# power.net
KiCad netlist of a schematic drawn in Altium Designer
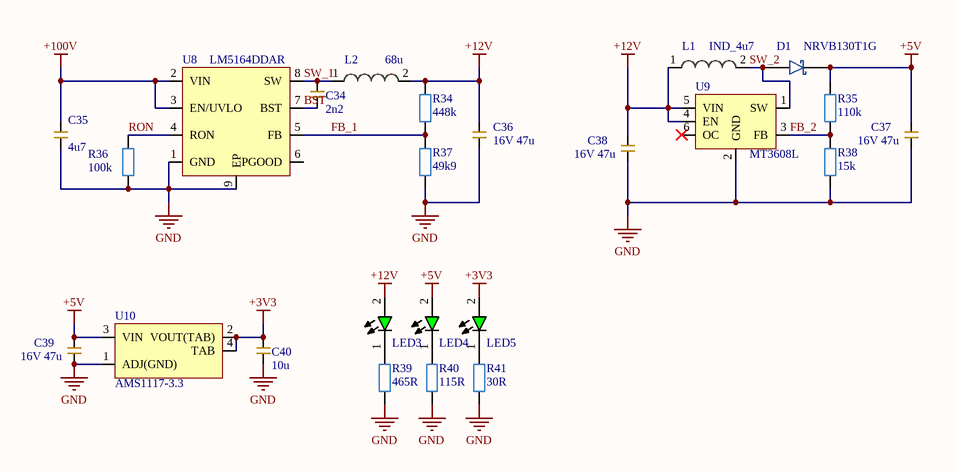
[diagram p0: power.SchDoc]

(export (version "E")
  (design (tool "Eeschema 10.0.6"))
  (components
    (comp (ref "C34")
      (value "2n2")
      (footprint "CAP_0603")
      (description "Multilayer Ceramic Capacitors MLCC - SMD/SMT ROHS")
      (libsource (lib "Passive") (part "CAP_0603"))
    )
    (comp (ref "C35")
      (value "4u7")
      (footprint "FS32X475K101EGG")
      (description "100V 4.7uF X7R ±10% 1210 Multilayer Ceramic Capacitors MLCC - SMD/SMT ROHS")
      (fields
        (field (name "MFR.") "PSA(Prosperity Dielectrics)")
        (field (name "MFR. PART") "FS32X475K101EGG")
      )
      (libsource (lib "Passive") (part "4u7"))
    )
    (comp (ref "C36")
      (value "16V 47u")
      (footprint "CAP_1210")
      (description "16V 47uF X5R ±10% 1210 Multilayer Ceramic Capacitors MLCC - SMD/SMT ROHS")
      (fields (field (name "MFR.") "Murata Electronics") (field (name "MFR. PART") "GRM32ER61C476KE15L"))
      (libsource (lib "Passive") (part "CAP_1210"))
    )
    (comp (ref "C37")
      (value "16V 47u")
      (footprint "CAP_1210")
      (description "16V 47uF X5R ±10% 1210 Multilayer Ceramic Capacitors MLCC - SMD/SMT ROHS")
      (fields (field (name "MFR.") "Murata Electronics") (field (name "MFR. PART") "GRM32ER61C476KE15L"))
      (libsource (lib "Passive") (part "CAP_1210"))
    )
    (comp (ref "C38")
      (value "16V 47u")
      (footprint "CAP_1210")
      (description "16V 47uF X5R ±10% 1210 Multilayer Ceramic Capacitors MLCC - SMD/SMT ROHS")
      (fields (field (name "MFR.") "Murata Electronics") (field (name "MFR. PART") "GRM32ER61C476KE15L"))
      (libsource (lib "Passive") (part "CAP_1210"))
    )
    (comp (ref "C39")
      (value "16V 47u")
      (footprint "CAP_1210")
      (description "16V 47uF X5R ±10% 1210 Multilayer Ceramic Capacitors MLCC - SMD/SMT ROHS")
      (fields (field (name "MFR.") "Murata Electronics") (field (name "MFR. PART") "GRM32ER61C476KE15L"))
      (libsource (lib "Passive") (part "CAP_1210"))
    )
    (comp (ref "C40")
      (value "10u")
      (footprint "CAP_0603")
      (description "Multilayer Ceramic Capacitors MLCC - SMD/SMT ROHS")
      (libsource (lib "Passive") (part "CAP_0603"))
    )
    (comp (ref "D1")
      (value "NRVB130T1G")
      (footprint "NRVB130T1G")
      (description "30V 1A 350mV@100mA SOD-123 Schottky Diodes ROHS")
      (fields (field (name "MFR.") "JSMSEMI"))
      (libsource (lib "Diodes") (part "NRVB130T1G"))
    )
    (comp (ref "L1")
      (value "IND_4u7")
      (footprint "FTC252010S4R7MBCA")
      (description "2A 4.7uH Integrated molded inductor ±20% 2.6A SMD,2x2.5mm Power Inductors ROHS")
      (fields
        (field (name "MFR.") "cjiang (Changjiang Microelectronics Tech)")
        (field (name "MFR. PART") "FTC252010S4R7MBCA")
      )
      (libsource (lib "Passive") (part "IND_4u7"))
    )
    (comp (ref "L2")
      (value "68u")
      (footprint "SMMS0650-680M")
      (description "1.5A 68uH Integrated molded inductor ±20% 2A SMD,6.6x7.1mm Power Inductors ROHS")
      (fields (field (name "MFR.") "SXN(Shun Xiang Nuo Elec)") (field (name "MFR. PART") "SMMS0650-680M"))
      (libsource (lib "Passive") (part "IND_68u"))
    )
    (comp (ref "LED3")
      (value "GREEN_0603")
      (footprint "GREEN_0603")
      (fields (field (name "MFR.") "XINGLIGHT") (field (name "MFR. PART") "XL-1608UGC-04"))
      (libsource (lib "LED") (part "GREEN_0603"))
    )
    (comp (ref "LED4")
      (value "GREEN_0603")
      (footprint "GREEN_0603")
      (fields (field (name "MFR.") "XINGLIGHT") (field (name "MFR. PART") "XL-1608UGC-04"))
      (libsource (lib "LED") (part "GREEN_0603"))
    )
    (comp (ref "LED5")
      (value "GREEN_0603")
      (footprint "GREEN_0603")
      (fields (field (name "MFR.") "XINGLIGHT") (field (name "MFR. PART") "XL-1608UGC-04"))
      (libsource (lib "LED") (part "GREEN_0603"))
    )
    (comp (ref "R34")
      (value "448k")
      (footprint "RES_0603")
      (description "100mW Thick Film Resistors")
      (libsource (lib "Passive") (part "RES_0603"))
    )
    (comp (ref "R35")
      (value "110k")
      (footprint "RES_0603")
      (description "100mW Thick Film Resistors")
      (libsource (lib "Passive") (part "RES_0603"))
    )
    (comp (ref "R36")
      (value "100k")
      (footprint "RES_0603")
      (description "100mW Thick Film Resistors")
      (libsource (lib "Passive") (part "RES_0603"))
    )
    (comp (ref "R37")
      (value "49k9")
      (footprint "RES_0603")
      (description "100mW Thick Film Resistors")
      (libsource (lib "Passive") (part "RES_0603"))
    )
    (comp (ref "R38")
      (value "15k")
      (footprint "RES_0603")
      (description "100mW Thick Film Resistors")
      (libsource (lib "Passive") (part "RES_0603"))
    )
    (comp (ref "R39")
      (value "465R")
      (footprint "RES_0603")
      (description "100mW Thick Film Resistors")
      (libsource (lib "Passive") (part "RES_0603"))
    )
    (comp (ref "R40")
      (value "115R")
      (footprint "RES_0603")
      (description "100mW Thick Film Resistors")
      (libsource (lib "Passive") (part "RES_0603"))
    )
    (comp (ref "R41")
      (value "30R")
      (footprint "RES_0603")
      (description "100mW Thick Film Resistors")
      (libsource (lib "Passive") (part "RES_0603"))
    )
    (comp (ref "U8")
      (value "LM5164DDAR")
      (footprint "LM5164DDAR")
      (description "Step-down type 1A 6V~100V SO-8-EP DC-DC Converters ROHS")
      (fields (field (name "MFR.") "Texas Instruments"))
      (libsource (lib "ICs") (part "LM5164DDAR"))
    )
    (comp (ref "U9")
      (value "MT3608L")
      (footprint "MT3608L")
      (description "2.2V~16V 2.5A SOT-23-6 DC-DC Converters ROHS")
      (fields (field (name "MFR.") "XI'AN Aerosemi Tech"))
      (libsource (lib "ICs") (part "MT3608L"))
    )
    (comp (ref "U10")
      (value "AMS1117-3.3")
      (footprint "AMS1117-3.3")
      (fields (field (name "MFR.") "UMW(Youtai Semiconductor Co., Ltd.)"))
      (libsource (lib "ICs") (part "AMS1117-3.3"))
    )
  )
  (nets
    (net (code "1") (name "+3V3") (class "Default")
      (node (ref "C40") (pin "2") (pintype "passive"))
      (node (ref "LED5") (pin "2") (pinfunction "A_2") (pintype "passive"))
      (node (ref "U10") (pin "2") (pinfunction "VOUT(TAB)_2") (pintype "passive"))
      (node (ref "U10") (pin "4") (pinfunction "TAB_4") (pintype "passive"))
    )
    (net (code "2") (name "+5V") (class "Default")
      (node (ref "C37") (pin "2") (pintype "passive"))
      (node (ref "C39") (pin "2") (pintype "passive"))
      (node (ref "D1") (pin "1") (pintype "passive"))
      (node (ref "LED4") (pin "2") (pinfunction "A_2") (pintype "passive"))
      (node (ref "R35") (pin "2") (pintype "passive"))
      (node (ref "U10") (pin "3") (pinfunction "VIN_3") (pintype "passive"))
    )
    (net (code "3") (name "+12V") (class "Default")
      (node (ref "C36") (pin "2") (pintype "passive"))
      (node (ref "C38") (pin "2") (pintype "passive"))
      (node (ref "L1") (pin "1") (pinfunction "1_1") (pintype "passive"))
      (node (ref "L2") (pin "2") (pinfunction "2_2") (pintype "passive"))
      (node (ref "LED3") (pin "2") (pinfunction "A_2") (pintype "passive"))
      (node (ref "R34") (pin "2") (pintype "passive"))
      (node (ref "U9") (pin "4") (pinfunction "EN_4") (pintype "passive"))
      (node (ref "U9") (pin "5") (pinfunction "VIN_5") (pintype "passive"))
    )
    (net (code "4") (name "+100V") (class "Default")
      (node (ref "C35") (pin "2") (pintype "passive"))
      (node (ref "U8") (pin "2") (pinfunction "VIN_2") (pintype "passive"))
      (node (ref "U8") (pin "3") (pinfunction "EN/UVLO_3") (pintype "passive"))
    )
    (net (code "5") (name "/BST") (class "Default")
      (node (ref "C34") (pin "1") (pintype "passive"))
      (node (ref "U8") (pin "7") (pinfunction "BST_7") (pintype "passive"))
    )
    (net (code "6") (name "/FB_1") (class "Default")
      (node (ref "R34") (pin "1") (pintype "passive"))
      (node (ref "R37") (pin "2") (pintype "passive"))
      (node (ref "U8") (pin "5") (pinfunction "FB_5") (pintype "passive"))
    )
    (net (code "7") (name "/FB_2") (class "Default")
      (node (ref "R35") (pin "1") (pintype "passive"))
      (node (ref "R38") (pin "2") (pintype "passive"))
      (node (ref "U9") (pin "3") (pinfunction "FB_3") (pintype "passive"))
    )
    (net (code "8") (name "/RON") (class "Default")
      (node (ref "R36") (pin "2") (pintype "passive"))
      (node (ref "U8") (pin "4") (pinfunction "RON_4") (pintype "passive"))
    )
    (net (code "9") (name "/SW_1") (class "Default")
      (node (ref "C34") (pin "2") (pintype "passive"))
      (node (ref "L2") (pin "1") (pinfunction "1_1") (pintype "passive"))
      (node (ref "U8") (pin "8") (pinfunction "SW_8") (pintype "passive"))
    )
    (net (code "10") (name "/SW_2") (class "Default")
      (node (ref "D1") (pin "2") (pintype "passive"))
      (node (ref "L1") (pin "2") (pinfunction "2_2") (pintype "passive"))
      (node (ref "U9") (pin "1") (pinfunction "SW_1") (pintype "passive"))
    )
    (net (code "11") (name "GND") (class "Default")
      (node (ref "C35") (pin "1") (pintype "passive"))
      (node (ref "C36") (pin "1") (pintype "passive"))
      (node (ref "C37") (pin "1") (pintype "passive"))
      (node (ref "C38") (pin "1") (pintype "passive"))
      (node (ref "C39") (pin "1") (pintype "passive"))
      (node (ref "C40") (pin "1") (pintype "passive"))
      (node (ref "R36") (pin "1") (pintype "passive"))
      (node (ref "R37") (pin "1") (pintype "passive"))
      (node (ref "R38") (pin "1") (pintype "passive"))
      (node (ref "R39") (pin "1") (pintype "passive"))
      (node (ref "R40") (pin "1") (pintype "passive"))
      (node (ref "R41") (pin "1") (pintype "passive"))
      (node (ref "U10") (pin "1") (pinfunction "ADJ(GND)_1") (pintype "passive"))
      (node (ref "U8") (pin "1") (pinfunction "GND_1") (pintype "passive"))
      (node (ref "U8") (pin "9") (pinfunction "EP_9") (pintype "passive"))
      (node (ref "U9") (pin "2") (pinfunction "GND_2") (pintype "passive"))
    )
    (net (code "12") (name "Net-(LED3-K)") (class "Default")
      (node (ref "LED3") (pin "1") (pinfunction "K_1") (pintype "passive"))
      (node (ref "R39") (pin "2") (pintype "passive"))
    )
    (net (code "13") (name "Net-(LED4-K)") (class "Default")
      (node (ref "LED4") (pin "1") (pinfunction "K_1") (pintype "passive"))
      (node (ref "R40") (pin "2") (pintype "passive"))
    )
    (net (code "14") (name "Net-(LED5-K)") (class "Default")
      (node (ref "LED5") (pin "1") (pinfunction "K_1") (pintype "passive"))
      (node (ref "R41") (pin "2") (pintype "passive"))
    )
    (net (code "15") (name "unconnected-(U8-PGOOD-Pad6)") (class "Default")
      (node (ref "U8") (pin "6") (pinfunction "PGOOD_6") (pintype "passive"))
    )
    (net (code "16") (name "unconnected-(U9-OC-Pad6)") (class "Default")
      (node (ref "U9") (pin "6") (pinfunction "OC_6") (pintype "passive+no_connect"))
    )
  )
)
